# Supply.net
KiCad netlist of a schematic drawn in Altium Designer
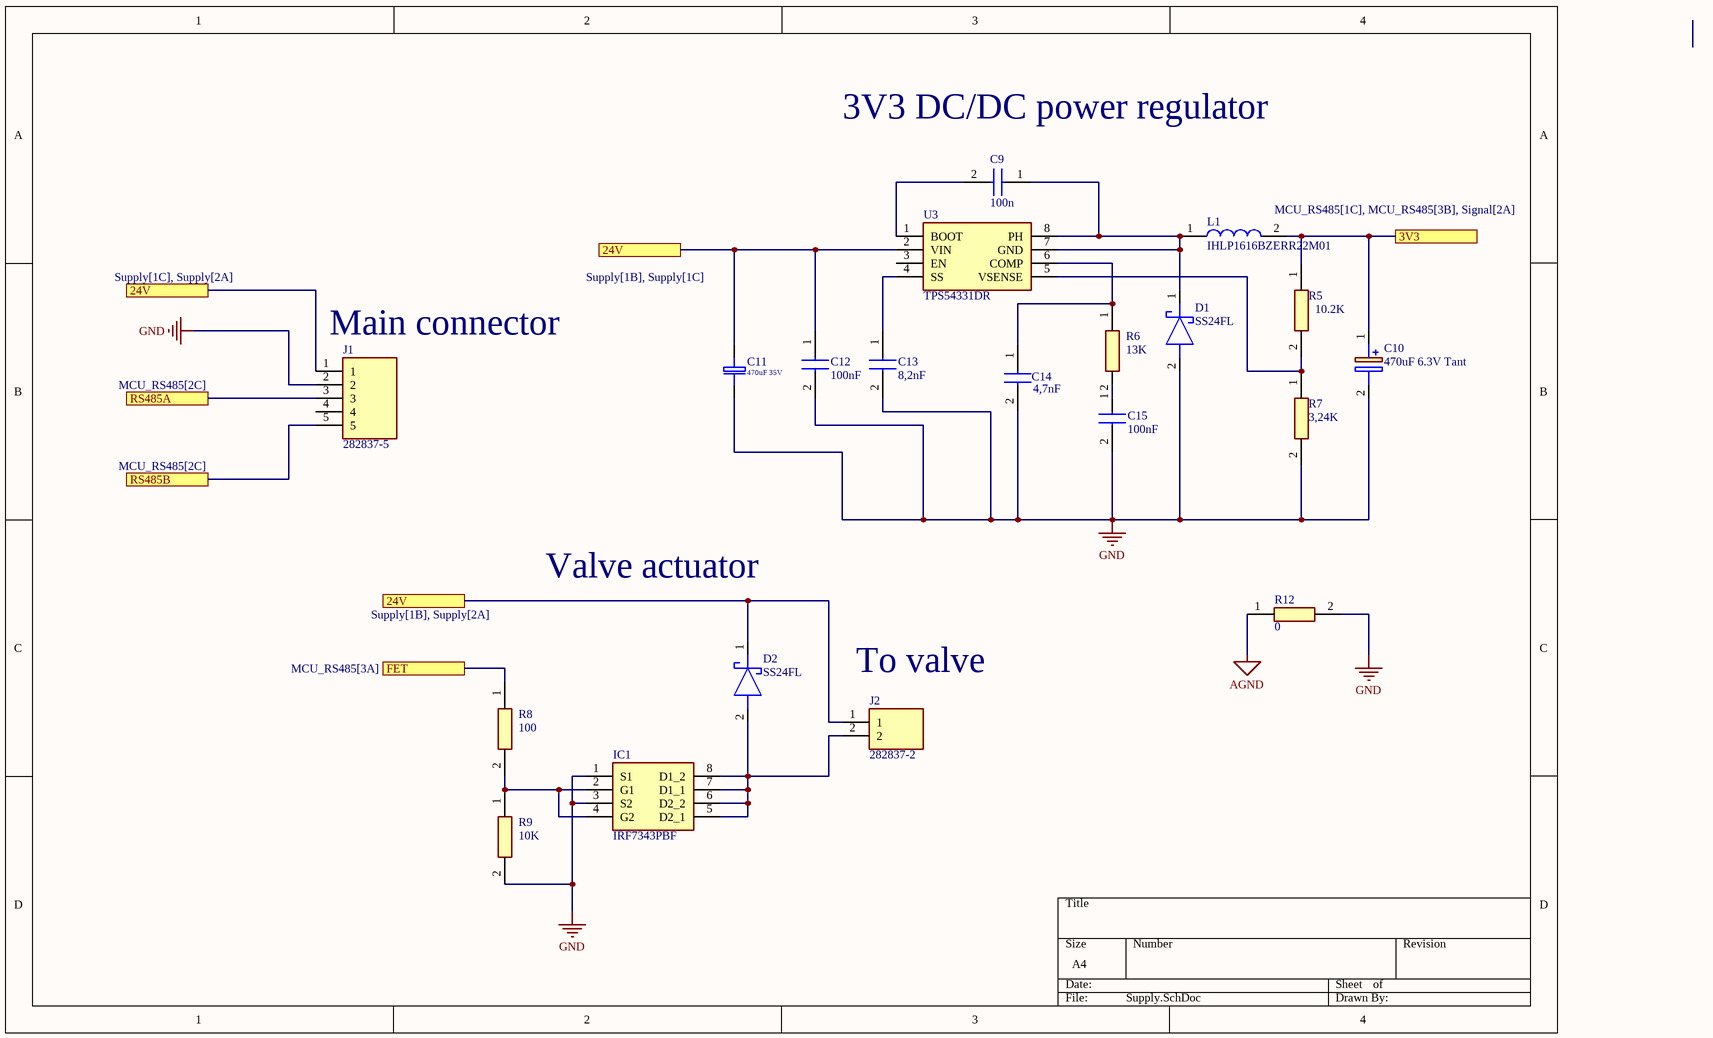
[diagram p0: Supply.SchDoc]

(export (version "E")
  (design (tool "Eeschema 10.0.6"))
  (components
    (comp (ref "C9")
      (value "100n")
      (footprint "SamacSys:CAPC2012X94N")
      (description "Capacitor")
      (fields
        (field (name "MANUFACTURER_PART_NUMBER") "08055A471FAT4A")
        (field (name "MOUSER PART NUMBER") "581-08055A471FAT4A")
      )
      (libsource (lib "*") (part "08055A471FAT4A"))
    )
    (comp (ref "C10")
      (value "470uF 6.3V Tant")
      (footprint "SamacSys:CAPPM6032X280N")
      (description "Capacitor Polarised")
      (fields
        (field (name "MANUFACTURER_PART_NUMBER") "TAJC477K004RNJ")
        (field (name "MOUSER PART NUMBER") "581-TAJC477K004RNJ")
      )
      (libsource (lib "*") (part "TAJC477K004RNJ"))
    )
    (comp (ref "C11")
      (value "470uF 35V")
      (footprint "El-d8-h12-F3.81")
      (description "35V-105F 0.5om 0.4A")
      (libsource (lib "PCB_Project") (part "100u-35V-105F"))
    )
    (comp (ref "C12")
      (value "100nF")
      (footprint "SamacSys:CAPC2012X94N")
      (description "Capacitor")
      (fields
        (field (name "MANUFACTURER_PART_NUMBER") "08055A471FAT4A")
        (field (name "MOUSER PART NUMBER") "581-08055A471FAT4A")
      )
      (libsource (lib "*") (part "08055A471FAT4A"))
    )
    (comp (ref "C13")
      (value "8,2nF")
      (footprint "SamacSys:CAPC2012X94N")
      (description "Capacitor")
      (fields
        (field (name "MANUFACTURER_PART_NUMBER") "08055A471FAT4A")
        (field (name "MOUSER PART NUMBER") "581-08055A471FAT4A")
      )
      (libsource (lib "*") (part "08055A471FAT4A"))
    )
    (comp (ref "C14")
      (value "4,7nF")
      (footprint "SamacSys:CAPC2012X94N")
      (description "Capacitor")
      (fields
        (field (name "MANUFACTURER_PART_NUMBER") "08055A471FAT4A")
        (field (name "MOUSER PART NUMBER") "581-08055A471FAT4A")
      )
      (libsource (lib "*") (part "08055A471FAT4A"))
    )
    (comp (ref "C15")
      (value "100nF")
      (footprint "SamacSys:CAPC2012X94N")
      (description "Capacitor")
      (fields
        (field (name "MANUFACTURER_PART_NUMBER") "08055A471FAT4A")
        (field (name "MOUSER PART NUMBER") "581-08055A471FAT4A")
      )
      (libsource (lib "*") (part "08055A471FAT4A"))
    )
    (comp (ref "D1")
      (value "SS24FL")
      (footprint "SamacSys:SODFL3617X108N")
      (description "Schottky Diode")
      (fields (field (name "MOUSER PART NUMBER") "512-SS24FL"))
      (libsource (lib "*") (part "SS24FL"))
    )
    (comp (ref "D2")
      (value "SS24FL")
      (footprint "SamacSys:SODFL3617X108N")
      (description "Schottky Diode")
      (fields (field (name "MOUSER PART NUMBER") "512-SS24FL"))
      (libsource (lib "*") (part "SS24FL"))
    )
    (comp (ref "IC1")
      (value "IRF7343PBF")
      (footprint "SamacSys:SOIC127P600X175-8N")
      (description "Integrated Circuit")
      (fields (field (name "MOUSER PART NUMBER") "942-IRF7343PBF"))
      (libsource (lib "*") (part "IRF7343PBF"))
    )
    (comp (ref "J1")
      (value "282837-5")
      (footprint "SamacSys:2828375")
      (description "Connector")
      (fields (field (name "MOUSER PART NUMBER") "571-2828375"))
      (libsource (lib "*") (part "282837-5"))
    )
    (comp (ref "J2")
      (value "282837-2")
      (footprint "SamacSys:2828372")
      (description "Connector")
      (fields (field (name "MOUSER PART NUMBER") "571-2828372"))
      (libsource (lib "*") (part "282837-2"))
    )
    (comp (ref "L1")
      (value "IHLP1616BZERR22M01")
      (footprint "SamacSys:INDPM4441X200N")
      (description "Inductor")
      (fields (field (name "MOUSER PART NUMBER") "70-IHLP1616BZERR22M0"))
      (libsource (lib "*") (part "IHLP1616BZERR22M01"))
    )
    (comp (ref "R5")
      (value "10.2K")
      (footprint "SamacSys:RESC2012X65N")
      (description "Resistor")
      (fields
        (field (name "MANUFACTURER_PART_NUMBER") "CPF0805B102KE1")
        (field (name "MOUSER PART NUMBER") "279-CPF0805B102KE1")
      )
      (libsource (lib "") (part "CPF0805B102KE1_1"))
    )
    (comp (ref "R6")
      (value "13K")
      (footprint "SamacSys:RESC2012X65N")
      (description "Resistor")
      (fields
        (field (name "MANUFACTURER_PART_NUMBER") "CPF0805B102KE1")
        (field (name "MOUSER PART NUMBER") "279-CPF0805B102KE1")
      )
      (libsource (lib "") (part "CPF0805B102KE1_1"))
    )
    (comp (ref "R7")
      (value "3,24K")
      (footprint "SamacSys:RESC2012X65N")
      (description "Resistor")
      (fields
        (field (name "MANUFACTURER_PART_NUMBER") "CPF0805B102KE1")
        (field (name "MOUSER PART NUMBER") "279-CPF0805B102KE1")
      )
      (libsource (lib "") (part "CPF0805B102KE1_1"))
    )
    (comp (ref "R8")
      (value "100")
      (footprint "SamacSys:RESC2012X65N")
      (description "Resistor")
      (fields
        (field (name "MANUFACTURER_PART_NUMBER") "CPF0805B102KE1")
        (field (name "MOUSER PART NUMBER") "279-CPF0805B102KE1")
      )
      (libsource (lib "") (part "CPF0805B102KE1_1"))
    )
    (comp (ref "R9")
      (value "10K")
      (footprint "SamacSys:RESC2012X65N")
      (description "Resistor")
      (fields
        (field (name "MANUFACTURER_PART_NUMBER") "CPF0805B102KE1")
        (field (name "MOUSER PART NUMBER") "279-CPF0805B102KE1")
      )
      (libsource (lib "") (part "CPF0805B102KE1_1"))
    )
    (comp (ref "R12")
      (value "0")
      (footprint "SamacSys:RESC2012X65N")
      (description "Resistor")
      (fields
        (field (name "MANUFACTURER_PART_NUMBER") "CPF0805B102KE1")
        (field (name "MOUSER PART NUMBER") "279-CPF0805B102KE1")
      )
      (libsource (lib "*") (part "CPF0805B102KE1"))
    )
    (comp (ref "U3")
      (value "TPS54331DR")
      (footprint "SamacSys:SOIC127P600X175-8N")
      (description "Integrated Circuit")
      (fields
        (field (name "MANUFACTURER_PART_NUMBER") "TPS54331D")
        (field (name "MOUSER PART NUMBER") "595-TPS54331D")
      )
      (libsource (lib "*") (part "TPS54331D"))
    )
  )
  (nets
    (net (code "1") (name "/3V3") (class "Default")
      (node (ref "C10") (pin "1") (pinfunction "+_1") (pintype "passive"))
      (node (ref "L1") (pin "2") (pinfunction "2_2") (pintype "passive"))
      (node (ref "R5") (pin "1") (pinfunction "1_1") (pintype "passive"))
    )
    (net (code "2") (name "/24V") (class "Default")
      (node (ref "C11") (pin "1") (pinfunction "1_1") (pintype "passive"))
      (node (ref "C12") (pin "1") (pinfunction "1_1") (pintype "passive"))
      (node (ref "D2") (pin "1") (pinfunction "K_1") (pintype "passive"))
      (node (ref "J1") (pin "1") (pinfunction "1_1") (pintype "passive"))
      (node (ref "J2") (pin "1") (pinfunction "1_1") (pintype "passive"))
      (node (ref "U3") (pin "2") (pinfunction "VIN_2") (pintype "passive"))
    )
    (net (code "3") (name "/FET") (class "Default")
      (node (ref "R8") (pin "1") (pinfunction "1_1") (pintype "passive"))
    )
    (net (code "4") (name "/RS485A") (class "Default")
      (node (ref "J1") (pin "3") (pinfunction "3_3") (pintype "passive"))
    )
    (net (code "5") (name "/RS485B") (class "Default")
      (node (ref "J1") (pin "5") (pinfunction "5_5") (pintype "passive"))
    )
    (net (code "6") (name "AGND") (class "Default")
      (node (ref "R12") (pin "1") (pinfunction "1_1") (pintype "passive"))
    )
    (net (code "7") (name "GND") (class "Default")
      (node (ref "C10") (pin "2") (pinfunction "-_2") (pintype "passive"))
      (node (ref "C11") (pin "2") (pinfunction "2_2") (pintype "passive"))
      (node (ref "C12") (pin "2") (pinfunction "2_2") (pintype "passive"))
      (node (ref "C13") (pin "2") (pinfunction "2_2") (pintype "passive"))
      (node (ref "C14") (pin "2") (pinfunction "2_2") (pintype "passive"))
      (node (ref "C15") (pin "2") (pinfunction "2_2") (pintype "passive"))
      (node (ref "D1") (pin "2") (pinfunction "A_2") (pintype "passive"))
      (node (ref "IC1") (pin "1") (pinfunction "S1_1") (pintype "passive"))
      (node (ref "IC1") (pin "3") (pinfunction "S2_3") (pintype "passive"))
      (node (ref "J1") (pin "2") (pinfunction "2_2") (pintype "passive"))
      (node (ref "R12") (pin "2") (pinfunction "2_2") (pintype "passive"))
      (node (ref "R7") (pin "2") (pinfunction "2_2") (pintype "passive"))
      (node (ref "R9") (pin "2") (pinfunction "2_2") (pintype "passive"))
    )
    (net (code "8") (name "Net-(C15-Pad1)") (class "Default")
      (node (ref "C15") (pin "1") (pinfunction "1_1") (pintype "passive"))
      (node (ref "R6") (pin "2") (pinfunction "2_2") (pintype "passive"))
    )
    (net (code "9") (name "Net-(D1-K)") (class "Default")
      (node (ref "C9") (pin "1") (pinfunction "1_1") (pintype "passive"))
      (node (ref "D1") (pin "1") (pinfunction "K_1") (pintype "passive"))
      (node (ref "L1") (pin "1") (pinfunction "1_1") (pintype "passive"))
      (node (ref "U3") (pin "7") (pinfunction "GND_7") (pintype "passive"))
      (node (ref "U3") (pin "8") (pinfunction "PH_8") (pintype "passive"))
    )
    (net (code "10") (name "Net-(D2-A)") (class "Default")
      (node (ref "D2") (pin "2") (pinfunction "A_2") (pintype "passive"))
      (node (ref "IC1") (pin "5") (pinfunction "D2_1_5") (pintype "passive"))
      (node (ref "IC1") (pin "6") (pinfunction "D2_2_6") (pintype "passive"))
      (node (ref "IC1") (pin "7") (pinfunction "D1_1_7") (pintype "passive"))
      (node (ref "IC1") (pin "8") (pinfunction "D1_2_8") (pintype "passive"))
      (node (ref "J2") (pin "2") (pinfunction "2_2") (pintype "passive"))
    )
    (net (code "11") (name "Net-(IC1-G1)") (class "Default")
      (node (ref "IC1") (pin "2") (pinfunction "G1_2") (pintype "passive"))
      (node (ref "IC1") (pin "4") (pinfunction "G2_4") (pintype "passive"))
      (node (ref "R8") (pin "2") (pinfunction "2_2") (pintype "passive"))
      (node (ref "R9") (pin "1") (pinfunction "1_1") (pintype "passive"))
    )
    (net (code "12") (name "Net-(U3-BOOT)") (class "Default")
      (node (ref "C9") (pin "2") (pinfunction "2_2") (pintype "passive"))
      (node (ref "U3") (pin "1") (pinfunction "BOOT_1") (pintype "passive"))
    )
    (net (code "13") (name "Net-(U3-COMP)") (class "Default")
      (node (ref "C14") (pin "1") (pinfunction "1_1") (pintype "passive"))
      (node (ref "R6") (pin "1") (pinfunction "1_1") (pintype "passive"))
      (node (ref "U3") (pin "6") (pinfunction "COMP_6") (pintype "passive"))
    )
    (net (code "14") (name "Net-(U3-SS)") (class "Default")
      (node (ref "C13") (pin "1") (pinfunction "1_1") (pintype "passive"))
      (node (ref "U3") (pin "4") (pinfunction "SS_4") (pintype "passive"))
    )
    (net (code "15") (name "Net-(U3-VSENSE)") (class "Default")
      (node (ref "R5") (pin "2") (pinfunction "2_2") (pintype "passive"))
      (node (ref "R7") (pin "1") (pinfunction "1_1") (pintype "passive"))
      (node (ref "U3") (pin "5") (pinfunction "VSENSE_5") (pintype "passive"))
    )
    (net (code "16") (name "unconnected-(J1-Pad4)") (class "Default")
      (node (ref "J1") (pin "4") (pinfunction "4_4") (pintype "passive"))
    )
    (net (code "17") (name "unconnected-(U3-EN-Pad3)") (class "Default")
      (node (ref "U3") (pin "3") (pinfunction "EN_3") (pintype "passive"))
    )
  )
)
